# zamekKodowy_odbiornik.net
KiCad netlist of a schematic drawn in EAGLE
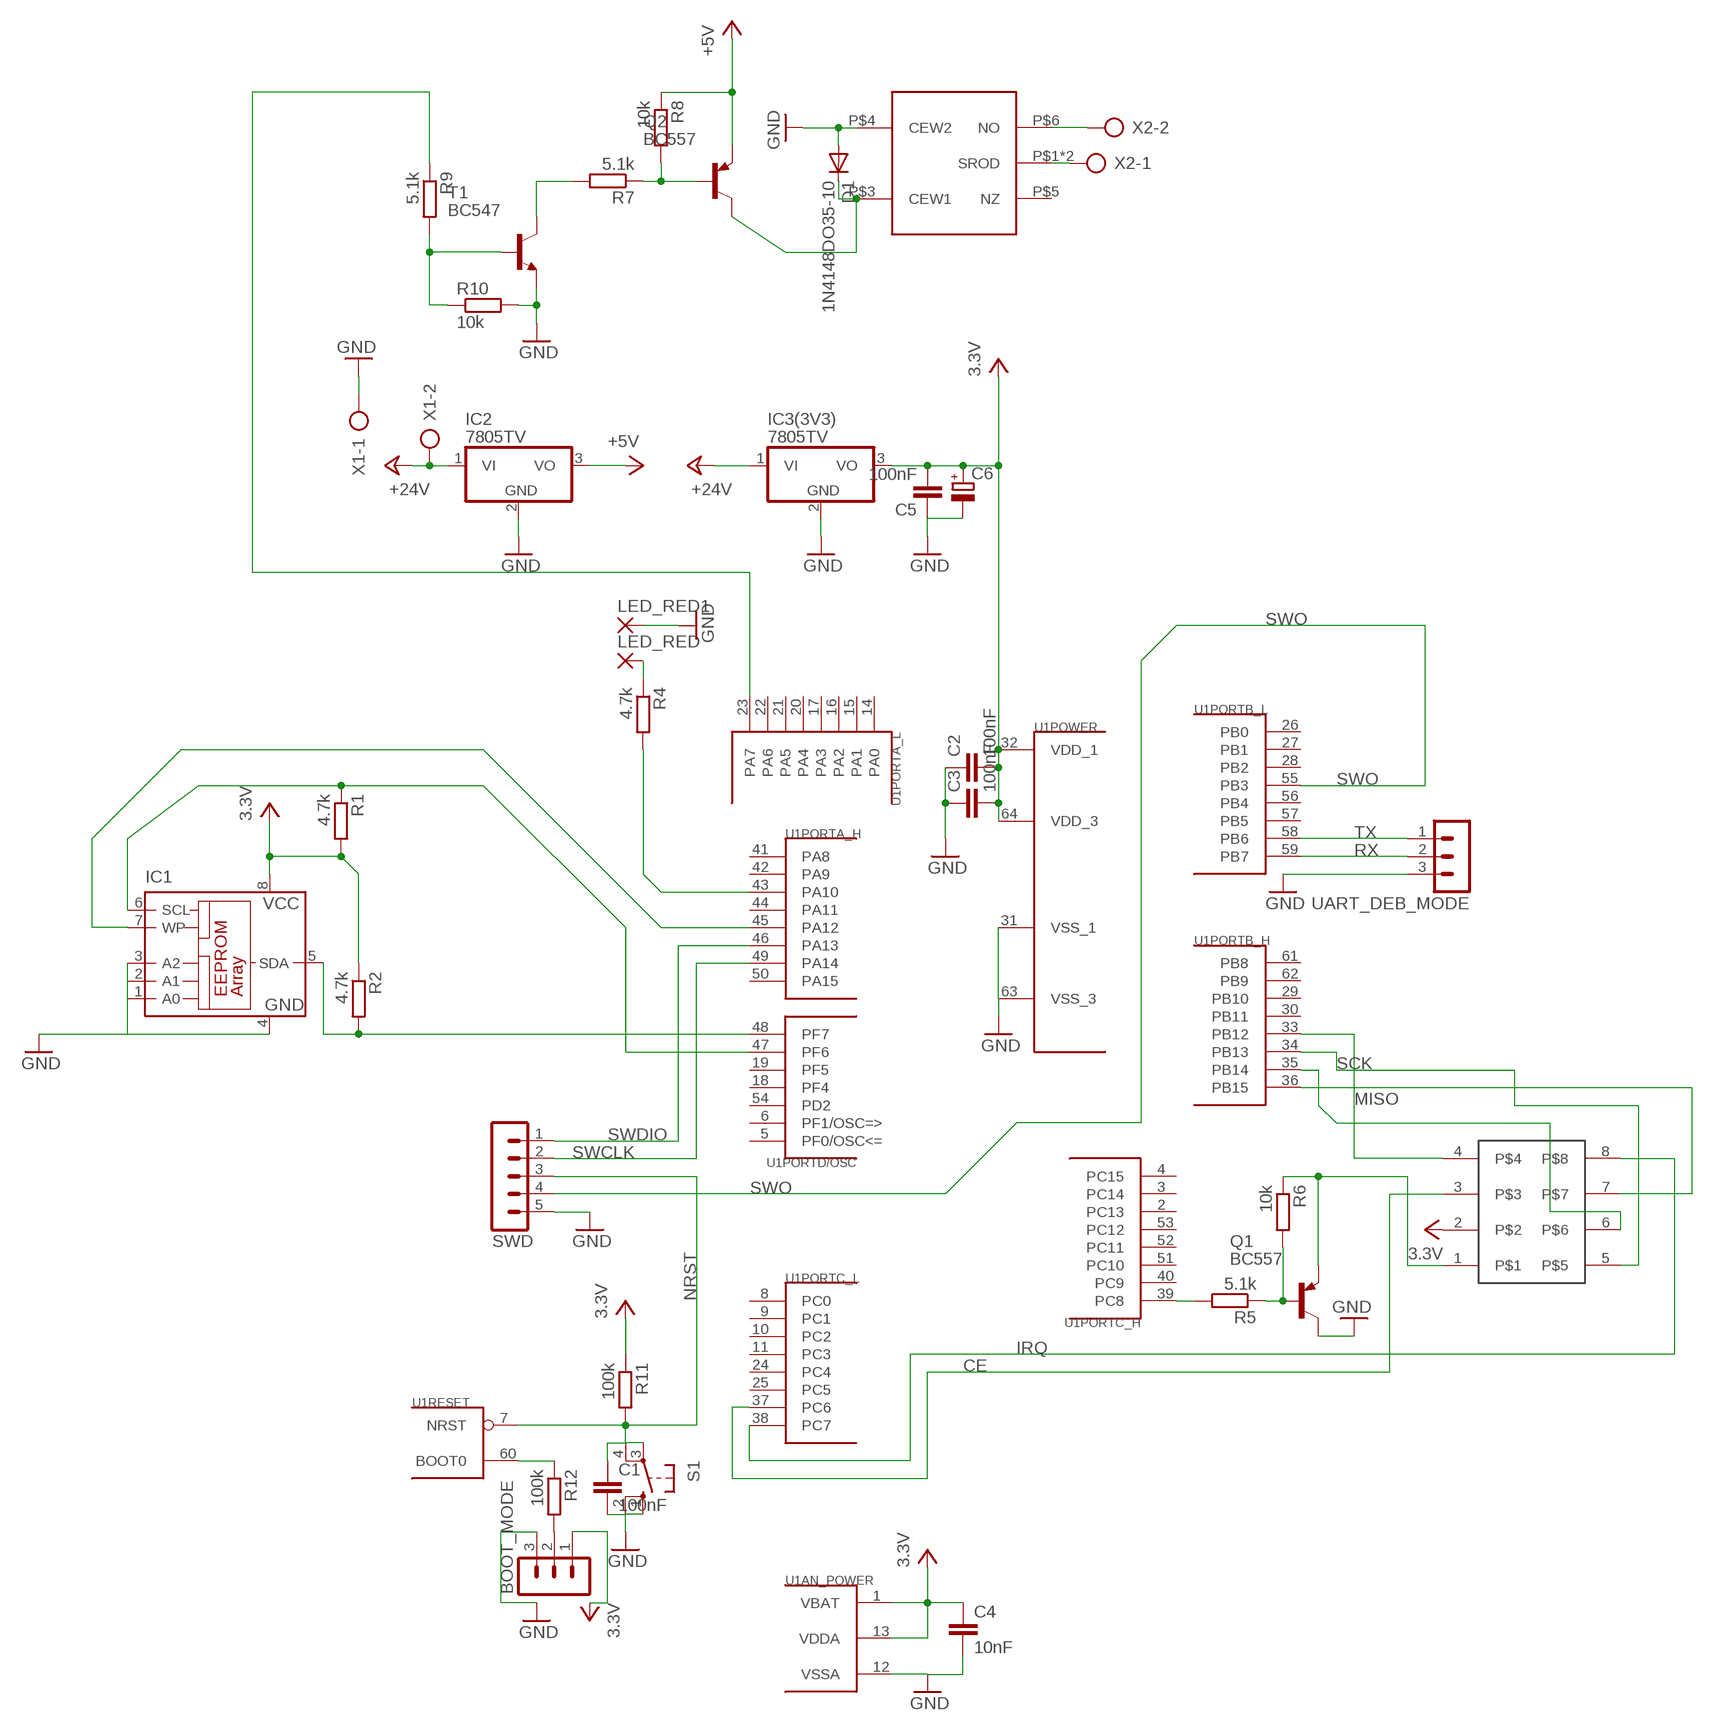
[diagram p0: schematic, sheet 1]

(export (version "E")
  (design (tool "Eeschema 10.0.6"))
  (components
    (comp (ref "BOOT_MODE")
      (value "MA03-1")
      (footprint "eagle-import:MA03-1")
      (fields (field (name "OC_FARNELL") "unknown") (field (name "OC_NEWARK") "unknown"))
      (libsource (lib "eagle-import") (part "MA03-1"))
    )
    (comp (ref "C1")
      (value "100nF")
      (footprint "eagle-import:C0603")
      (libsource (lib "eagle-import") (part "C-EUC0603"))
    )
    (comp (ref "C2")
      (value "100nF")
      (footprint "eagle-import:C0603")
      (libsource (lib "eagle-import") (part "C-EUC0603"))
    )
    (comp (ref "C3")
      (value "100nF")
      (footprint "eagle-import:C0603")
      (libsource (lib "eagle-import") (part "C-EUC0603"))
    )
    (comp (ref "C4")
      (value "10nF")
      (footprint "eagle-import:C0603")
      (libsource (lib "eagle-import") (part "C-EUC0603"))
    )
    (comp (ref "C5")
      (value "100nF")
      (footprint "eagle-import:C0603")
      (libsource (lib "eagle-import") (part "C-EUC0603"))
    )
    (comp (ref "C6")
      (value "CPOL-EUE2-5")
      (footprint "eagle-import:E2-5")
      (libsource (lib "eagle-import") (part "CPOL-EUE2-5"))
    )
    (comp (ref "CON1")
      (value "CON10")
      (footprint "eagle-import:CON10")
      (libsource (lib "eagle-import") (part "CON10"))
    )
    (comp (ref "D1")
      (value "1N4148DO35-10")
      (footprint "eagle-import:DO35-10")
      (libsource (lib "eagle-import") (part "1N4148DO35-10"))
    )
    (comp (ref "IC1")
      (value "24C16BSN")
      (footprint "eagle-import:SO-08")
      (fields (field (name "MPN") "AT24C16BN-SH-B"))
      (libsource (lib "eagle-import") (part "24SNC16B"))
    )
    (comp (ref "IC2")
      (value "7805TV")
      (footprint "eagle-import:TO220V")
      (libsource (lib "eagle-import") (part "78TV05"))
    )
    (comp (ref "IC3(3V3)")
      (value "7805TV")
      (footprint "eagle-import:TO220V")
      (libsource (lib "eagle-import") (part "78TV05"))
    )
    (comp (ref "LED_RED")
      (value "2,54/0,9")
      (footprint "eagle-import:2,54_0,9")
      (libsource (lib "eagle-import") (part "2,54/0,9"))
    )
    (comp (ref "LED_RED1")
      (value "2,54/0,9")
      (footprint "eagle-import:2,54_0,9")
      (libsource (lib "eagle-import") (part "2,54/0,9"))
    )
    (comp (ref "Q1")
      (value "BC557")
      (footprint "eagle-import:TO92")
      (libsource (lib "eagle-import") (part "BC557"))
    )
    (comp (ref "Q2")
      (value "BC557")
      (footprint "eagle-import:TO92")
      (libsource (lib "eagle-import") (part "BC557"))
    )
    (comp (ref "R1")
      (value "4.7k")
      (footprint "eagle-import:R0603")
      (libsource (lib "eagle-import") (part "R-EU_R0603"))
    )
    (comp (ref "R2")
      (value "4.7k")
      (footprint "eagle-import:R0603")
      (libsource (lib "eagle-import") (part "R-EU_R0603"))
    )
    (comp (ref "R4")
      (value "4.7k")
      (footprint "eagle-import:R0603")
      (libsource (lib "eagle-import") (part "R-EU_R0603"))
    )
    (comp (ref "R5")
      (value "5.1k")
      (footprint "eagle-import:R0603")
      (libsource (lib "eagle-import") (part "R-EU_R0603"))
    )
    (comp (ref "R6")
      (value "10k")
      (footprint "eagle-import:R0603")
      (libsource (lib "eagle-import") (part "R-EU_R0603"))
    )
    (comp (ref "R7")
      (value "5.1k")
      (footprint "eagle-import:R0603")
      (libsource (lib "eagle-import") (part "R-EU_R0603"))
    )
    (comp (ref "R8")
      (value "10k")
      (footprint "eagle-import:R0603")
      (libsource (lib "eagle-import") (part "R-EU_R0603"))
    )
    (comp (ref "R9")
      (value "5.1k")
      (footprint "eagle-import:R0603")
      (libsource (lib "eagle-import") (part "R-EU_R0603"))
    )
    (comp (ref "R10")
      (value "10k")
      (footprint "eagle-import:R0603")
      (libsource (lib "eagle-import") (part "R-EU_R0603"))
    )
    (comp (ref "R11")
      (value "100k")
      (footprint "eagle-import:R0603")
      (libsource (lib "eagle-import") (part "R-EU_R0603"))
    )
    (comp (ref "R12")
      (value "100k")
      (footprint "eagle-import:R0603")
      (libsource (lib "eagle-import") (part "R-EU_R0603"))
    )
    (comp (ref "S1")
      (value "10-XX")
      (footprint "eagle-import:B3F-10XX")
      (fields (field (name "MPN") "B3F-1000"))
      (libsource (lib "eagle-import") (part "10-XX"))
    )
    (comp (ref "SWD")
      (value "MA05-1")
      (footprint "eagle-import:MA05-1")
      (libsource (lib "eagle-import") (part "MA05-1"))
    )
    (comp (ref "T1")
      (value "BC547")
      (footprint "eagle-import:TO92")
      (libsource (lib "eagle-import") (part "BC547"))
    )
    (comp (ref "U$1")
      (value "PRZEKAZ")
      (footprint "eagle-import:FPR")
      (libsource (lib "eagle-import") (part "PRZEKAZ"))
    )
    (comp (ref "U1")
      (value "STM32F10XRXT6")
      (footprint "eagle-import:TQFP64")
      (libsource (lib "eagle-import") (part "STM32F10XRXT6"))
    )
    (comp (ref "UART_DEB_MODE")
      (value "MA03-1")
      (footprint "eagle-import:MA03-1")
      (libsource (lib "eagle-import") (part "MA03-1"))
    )
    (comp (ref "X1")
      (value "AK300/2")
      (footprint "eagle-import:AK300_2")
      (libsource (lib "eagle-import") (part "AK300/2"))
    )
    (comp (ref "X2")
      (value "AK300/2")
      (footprint "eagle-import:AK300_2")
      (libsource (lib "eagle-import") (part "AK300/2"))
    )
  )
  (nets
    (net (code "1") (name "+5V") (class "Default")
      (node (ref "IC2") (pin "3") (pinfunction "VO_3") (pintype "passive"))
      (node (ref "Q2") (pin "1") (pinfunction "E_1") (pintype "passive"))
      (node (ref "R8") (pin "1") (pinfunction "1_1") (pintype "passive"))
    )
    (net (code "2") (name "+24V") (class "Default")
      (node (ref "IC2") (pin "1") (pinfunction "VI_1") (pintype "input"))
      (node (ref "IC3(3V3)") (pin "1") (pinfunction "VI_1") (pintype "input"))
      (node (ref "X1") (pin "2") (pinfunction "KL_2") (pintype "passive"))
    )
    (net (code "3") (name "/CE") (class "Default")
      (node (ref "CON1") (pin "3") (pinfunction "P$3_3") (pintype "bidirectional"))
      (node (ref "U1") (pin "37") (pinfunction "PC6_37") (pintype "bidirectional"))
    )
    (net (code "4") (name "/IRQ") (class "Default")
      (node (ref "CON1") (pin "8") (pinfunction "P$8_8") (pintype "bidirectional"))
      (node (ref "U1") (pin "38") (pinfunction "PC7_38") (pintype "bidirectional"))
    )
    (net (code "5") (name "/MISO") (class "Default")
      (node (ref "CON1") (pin "7") (pinfunction "P$7_7") (pintype "bidirectional"))
      (node (ref "U1") (pin "36") (pinfunction "PB15_36") (pintype "bidirectional"))
    )
    (net (code "6") (name "/NRST") (class "Default")
      (node (ref "C1") (pin "1") (pinfunction "1_1") (pintype "passive"))
      (node (ref "R11") (pin "2") (pinfunction "2_2") (pintype "passive"))
      (node (ref "S1") (pin "3") (pinfunction "P_3") (pintype "passive"))
      (node (ref "S1") (pin "4") (pinfunction "P1_4") (pintype "passive"))
      (node (ref "SWD") (pin "3") (pinfunction "3_3") (pintype "passive"))
      (node (ref "U1") (pin "7") (pinfunction "NRST_7") (pintype "input"))
    )
    (net (code "7") (name "/RX") (class "Default")
      (node (ref "U1") (pin "59") (pinfunction "PB7_59") (pintype "bidirectional"))
      (node (ref "UART_DEB_MODE") (pin "2") (pinfunction "2_2") (pintype "passive"))
    )
    (net (code "8") (name "/SCK") (class "Default")
      (node (ref "CON1") (pin "5") (pinfunction "P$5_5") (pintype "bidirectional"))
      (node (ref "U1") (pin "34") (pinfunction "PB13_34") (pintype "bidirectional"))
    )
    (net (code "9") (name "/SWCLK") (class "Default")
      (node (ref "SWD") (pin "2") (pinfunction "2_2") (pintype "passive"))
      (node (ref "U1") (pin "49") (pinfunction "PA14_49") (pintype "bidirectional"))
    )
    (net (code "10") (name "/SWDIO") (class "Default")
      (node (ref "SWD") (pin "1") (pinfunction "1_1") (pintype "passive"))
      (node (ref "U1") (pin "46") (pinfunction "PA13_46") (pintype "bidirectional"))
    )
    (net (code "11") (name "/SWO") (class "Default")
      (node (ref "SWD") (pin "4") (pinfunction "4_4") (pintype "passive"))
      (node (ref "U1") (pin "55") (pinfunction "PB3_55") (pintype "bidirectional"))
    )
    (net (code "12") (name "/TX") (class "Default")
      (node (ref "U1") (pin "58") (pinfunction "PB6_58") (pintype "bidirectional"))
      (node (ref "UART_DEB_MODE") (pin "1") (pinfunction "1_1") (pintype "passive"))
    )
    (net (code "13") (name "3.3V") (class "Default")
      (node (ref "BOOT_MODE") (pin "1") (pinfunction "1_1") (pintype "passive"))
      (node (ref "C2") (pin "2") (pinfunction "2_2") (pintype "passive"))
      (node (ref "C3") (pin "2") (pinfunction "2_2") (pintype "passive"))
      (node (ref "C4") (pin "1") (pinfunction "1_1") (pintype "passive"))
      (node (ref "C5") (pin "2") (pinfunction "2_2") (pintype "passive"))
      (node (ref "C6") (pin "+") (pinfunction "+_+") (pintype "passive"))
      (node (ref "CON1") (pin "2") (pinfunction "P$2_2") (pintype "bidirectional"))
      (node (ref "IC1") (pin "8") (pinfunction "VCC_8") (pintype "power_in"))
      (node (ref "IC3(3V3)") (pin "3") (pinfunction "VO_3") (pintype "passive"))
      (node (ref "R1") (pin "2") (pinfunction "2_2") (pintype "passive"))
      (node (ref "R11") (pin "1") (pinfunction "1_1") (pintype "passive"))
      (node (ref "R2") (pin "1") (pinfunction "1_1") (pintype "passive"))
      (node (ref "U1") (pin "1") (pinfunction "VBAT_1") (pintype "power_in"))
      (node (ref "U1") (pin "13") (pinfunction "VDDA_13") (pintype "power_in"))
      (node (ref "U1") (pin "32") (pinfunction "VDD_1_32") (pintype "power_in"))
      (node (ref "U1") (pin "64") (pinfunction "VDD_3_64") (pintype "power_in"))
    )
    (net (code "14") (name "GND") (class "Default")
      (node (ref "BOOT_MODE") (pin "3") (pinfunction "3_3") (pintype "passive"))
      (node (ref "C1") (pin "2") (pinfunction "2_2") (pintype "passive"))
      (node (ref "C2") (pin "1") (pinfunction "1_1") (pintype "passive"))
      (node (ref "C3") (pin "1") (pinfunction "1_1") (pintype "passive"))
      (node (ref "C4") (pin "2") (pinfunction "2_2") (pintype "passive"))
      (node (ref "C5") (pin "1") (pinfunction "1_1") (pintype "passive"))
      (node (ref "C6") (pin "-") (pinfunction "-_-") (pintype "passive"))
      (node (ref "D1") (pin "A") (pinfunction "A_A") (pintype "passive"))
      (node (ref "IC1") (pin "1") (pinfunction "A0_1") (pintype "input"))
      (node (ref "IC1") (pin "2") (pinfunction "A1_2") (pintype "input"))
      (node (ref "IC1") (pin "3") (pinfunction "A2_3") (pintype "input"))
      (node (ref "IC1") (pin "4") (pinfunction "GND_4") (pintype "power_in"))
      (node (ref "IC2") (pin "2") (pinfunction "GND_2") (pintype "passive"))
      (node (ref "IC3(3V3)") (pin "2") (pinfunction "GND_2") (pintype "passive"))
      (node (ref "LED_RED1") (pin "1") (pinfunction "P_1") (pintype "passive"))
      (node (ref "Q1") (pin "3") (pinfunction "C_3") (pintype "passive"))
      (node (ref "R10") (pin "2") (pinfunction "2_2") (pintype "passive"))
      (node (ref "S1") (pin "1") (pinfunction "S_1") (pintype "passive"))
      (node (ref "S1") (pin "2") (pinfunction "S1_2") (pintype "passive"))
      (node (ref "SWD") (pin "5") (pinfunction "5_5") (pintype "passive"))
      (node (ref "T1") (pin "1") (pinfunction "E_1") (pintype "passive"))
      (node (ref "U$1") (pin "P$4") (pinfunction "CEW2_P$4") (pintype "bidirectional"))
      (node (ref "U1") (pin "12") (pinfunction "VSSA_12") (pintype "power_in"))
      (node (ref "U1") (pin "31") (pinfunction "VSS_1_31") (pintype "power_in"))
      (node (ref "U1") (pin "63") (pinfunction "VSS_3_63") (pintype "power_in"))
      (node (ref "UART_DEB_MODE") (pin "3") (pinfunction "3_3") (pintype "passive"))
      (node (ref "X1") (pin "1") (pinfunction "KL_1") (pintype "passive"))
    )
    (net (code "15") (name "Net-(BOOT_MODE-Pad2)") (class "Default")
      (node (ref "BOOT_MODE") (pin "2") (pinfunction "2_2") (pintype "passive"))
      (node (ref "R12") (pin "2") (pinfunction "2_2") (pintype "passive"))
    )
    (net (code "16") (name "Net-(CON1-P$1)") (class "Default")
      (node (ref "CON1") (pin "1") (pinfunction "P$1_1") (pintype "bidirectional"))
      (node (ref "Q1") (pin "1") (pinfunction "E_1") (pintype "passive"))
      (node (ref "R6") (pin "1") (pinfunction "1_1") (pintype "passive"))
    )
    (net (code "17") (name "Net-(CON1-P$4)") (class "Default")
      (node (ref "CON1") (pin "4") (pinfunction "P$4_4") (pintype "bidirectional"))
      (node (ref "U1") (pin "33") (pinfunction "PB12_33") (pintype "bidirectional"))
    )
    (net (code "18") (name "Net-(CON1-P$6)") (class "Default")
      (node (ref "CON1") (pin "6") (pinfunction "P$6_6") (pintype "bidirectional"))
      (node (ref "U1") (pin "35") (pinfunction "PB14_35") (pintype "bidirectional"))
    )
    (net (code "19") (name "Net-(IC1-SCL)") (class "Default")
      (node (ref "IC1") (pin "6") (pinfunction "SCL_6") (pintype "input"))
      (node (ref "R1") (pin "1") (pinfunction "1_1") (pintype "passive"))
      (node (ref "U1") (pin "47") (pinfunction "PF6_47") (pintype "bidirectional"))
    )
    (net (code "20") (name "Net-(IC1-SDA)") (class "Default")
      (node (ref "IC1") (pin "5") (pinfunction "SDA_5") (pintype "bidirectional"))
      (node (ref "R2") (pin "2") (pinfunction "2_2") (pintype "passive"))
      (node (ref "U1") (pin "48") (pinfunction "PF7_48") (pintype "bidirectional"))
    )
    (net (code "21") (name "Net-(IC1-WP)") (class "Default")
      (node (ref "IC1") (pin "7") (pinfunction "WP_7") (pintype "input"))
      (node (ref "U1") (pin "45") (pinfunction "PA12_45") (pintype "bidirectional"))
    )
    (net (code "22") (name "Net-(LED_RED-P)") (class "Default")
      (node (ref "LED_RED") (pin "1") (pinfunction "P_1") (pintype "passive"))
      (node (ref "R4") (pin "1") (pinfunction "1_1") (pintype "passive"))
    )
    (net (code "23") (name "Net-(Q1-B)") (class "Default")
      (node (ref "Q1") (pin "2") (pinfunction "B_2") (pintype "passive"))
      (node (ref "R5") (pin "1") (pinfunction "1_1") (pintype "passive"))
      (node (ref "R6") (pin "2") (pinfunction "2_2") (pintype "passive"))
    )
    (net (code "24") (name "Net-(Q2-B)") (class "Default")
      (node (ref "Q2") (pin "2") (pinfunction "B_2") (pintype "passive"))
      (node (ref "R7") (pin "1") (pinfunction "1_1") (pintype "passive"))
      (node (ref "R8") (pin "2") (pinfunction "2_2") (pintype "passive"))
    )
    (net (code "25") (name "Net-(Q2-C)") (class "Default")
      (node (ref "D1") (pin "C") (pinfunction "C_C") (pintype "passive"))
      (node (ref "Q2") (pin "3") (pinfunction "C_3") (pintype "passive"))
      (node (ref "U$1") (pin "P$3") (pinfunction "CEW1_P$3") (pintype "bidirectional"))
    )
    (net (code "26") (name "Net-(T1-B)") (class "Default")
      (node (ref "R10") (pin "1") (pinfunction "1_1") (pintype "passive"))
      (node (ref "R9") (pin "2") (pinfunction "2_2") (pintype "passive"))
      (node (ref "T1") (pin "2") (pinfunction "B_2") (pintype "passive"))
    )
    (net (code "27") (name "Net-(T1-C)") (class "Default")
      (node (ref "R7") (pin "2") (pinfunction "2_2") (pintype "passive"))
      (node (ref "T1") (pin "3") (pinfunction "C_3") (pintype "passive"))
    )
    (net (code "28") (name "Net-(U$1-NO)") (class "Default")
      (node (ref "U$1") (pin "P$6") (pinfunction "NO_P$6") (pintype "bidirectional"))
      (node (ref "X2") (pin "2") (pinfunction "KL_2") (pintype "passive"))
    )
    (net (code "29") (name "Net-(U1B-PA10)") (class "Default")
      (node (ref "R4") (pin "2") (pinfunction "2_2") (pintype "passive"))
      (node (ref "U1") (pin "43") (pinfunction "PA10_43") (pintype "bidirectional"))
    )
    (net (code "30") (name "Net-(U1C-PA7)") (class "Default")
      (node (ref "R9") (pin "1") (pinfunction "1_1") (pintype "passive"))
      (node (ref "U1") (pin "23") (pinfunction "PA7_23") (pintype "bidirectional"))
    )
    (net (code "31") (name "Net-(U1F-PC8)") (class "Default")
      (node (ref "R5") (pin "2") (pinfunction "2_2") (pintype "passive"))
      (node (ref "U1") (pin "39") (pinfunction "PC8_39") (pintype "bidirectional"))
    )
    (net (code "32") (name "Net-(U1J-BOOT0)") (class "Default")
      (node (ref "R12") (pin "1") (pinfunction "1_1") (pintype "passive"))
      (node (ref "U1") (pin "60") (pinfunction "BOOT0_60") (pintype "input"))
    )
    (net (code "33") (name "Net-(X2A-KL)") (class "Default")
      (node (ref "U$1") (pin "P$1") (pinfunction "SROD_P$1") (pintype "bidirectional"))
      (node (ref "U$1") (pin "P$2") (pinfunction "SROD_P$2") (pintype "bidirectional"))
      (node (ref "X2") (pin "1") (pinfunction "KL_1") (pintype "passive"))
    )
    (net (code "34") (name "unconnected-(U$1-NZ-PadP$5)") (class "Default")
      (node (ref "U$1") (pin "P$5") (pinfunction "NZ_P$5") (pintype "bidirectional"))
    )
    (net (code "35") (name "unconnected-(U1B-PA8-Pad41)") (class "Default")
      (node (ref "U1") (pin "41") (pinfunction "PA8_41") (pintype "bidirectional"))
    )
    (net (code "36") (name "unconnected-(U1B-PA9-Pad42)") (class "Default")
      (node (ref "U1") (pin "42") (pinfunction "PA9_42") (pintype "bidirectional"))
    )
    (net (code "37") (name "unconnected-(U1B-PA11-Pad44)") (class "Default")
      (node (ref "U1") (pin "44") (pinfunction "PA11_44") (pintype "bidirectional"))
    )
    (net (code "38") (name "unconnected-(U1B-PA15-Pad50)") (class "Default")
      (node (ref "U1") (pin "50") (pinfunction "PA15_50") (pintype "bidirectional"))
    )
    (net (code "39") (name "unconnected-(U1C-PA0-Pad14)") (class "Default")
      (node (ref "U1") (pin "14") (pinfunction "PA0_14") (pintype "bidirectional"))
    )
    (net (code "40") (name "unconnected-(U1C-PA1-Pad15)") (class "Default")
      (node (ref "U1") (pin "15") (pinfunction "PA1_15") (pintype "bidirectional"))
    )
    (net (code "41") (name "unconnected-(U1C-PA2-Pad16)") (class "Default")
      (node (ref "U1") (pin "16") (pinfunction "PA2_16") (pintype "bidirectional"))
    )
    (net (code "42") (name "unconnected-(U1C-PA3-Pad17)") (class "Default")
      (node (ref "U1") (pin "17") (pinfunction "PA3_17") (pintype "bidirectional"))
    )
    (net (code "43") (name "unconnected-(U1C-PA4-Pad20)") (class "Default")
      (node (ref "U1") (pin "20") (pinfunction "PA4_20") (pintype "bidirectional"))
    )
    (net (code "44") (name "unconnected-(U1C-PA5-Pad21)") (class "Default")
      (node (ref "U1") (pin "21") (pinfunction "PA5_21") (pintype "bidirectional"))
    )
    (net (code "45") (name "unconnected-(U1C-PA6-Pad22)") (class "Default")
      (node (ref "U1") (pin "22") (pinfunction "PA6_22") (pintype "bidirectional"))
    )
    (net (code "46") (name "unconnected-(U1D-PB8-Pad61)") (class "Default")
      (node (ref "U1") (pin "61") (pinfunction "PB8_61") (pintype "bidirectional"))
    )
    (net (code "47") (name "unconnected-(U1D-PB9-Pad62)") (class "Default")
      (node (ref "U1") (pin "62") (pinfunction "PB9_62") (pintype "bidirectional"))
    )
    (net (code "48") (name "unconnected-(U1D-PB10-Pad29)") (class "Default")
      (node (ref "U1") (pin "29") (pinfunction "PB10_29") (pintype "bidirectional"))
    )
    (net (code "49") (name "unconnected-(U1D-PB11-Pad30)") (class "Default")
      (node (ref "U1") (pin "30") (pinfunction "PB11_30") (pintype "bidirectional"))
    )
    (net (code "50") (name "unconnected-(U1E-PB0-Pad26)") (class "Default")
      (node (ref "U1") (pin "26") (pinfunction "PB0_26") (pintype "bidirectional"))
    )
    (net (code "51") (name "unconnected-(U1E-PB1-Pad27)") (class "Default")
      (node (ref "U1") (pin "27") (pinfunction "PB1_27") (pintype "bidirectional"))
    )
    (net (code "52") (name "unconnected-(U1E-PB2-Pad28)") (class "Default")
      (node (ref "U1") (pin "28") (pinfunction "PB2_28") (pintype "bidirectional"))
    )
    (net (code "53") (name "unconnected-(U1E-PB4-Pad56)") (class "Default")
      (node (ref "U1") (pin "56") (pinfunction "PB4_56") (pintype "bidirectional"))
    )
    (net (code "54") (name "unconnected-(U1E-PB5-Pad57)") (class "Default")
      (node (ref "U1") (pin "57") (pinfunction "PB5_57") (pintype "bidirectional"))
    )
    (net (code "55") (name "unconnected-(U1F-PC9-Pad40)") (class "Default")
      (node (ref "U1") (pin "40") (pinfunction "PC9_40") (pintype "bidirectional"))
    )
    (net (code "56") (name "unconnected-(U1F-PC10-Pad51)") (class "Default")
      (node (ref "U1") (pin "51") (pinfunction "PC10_51") (pintype "bidirectional"))
    )
    (net (code "57") (name "unconnected-(U1F-PC11-Pad52)") (class "Default")
      (node (ref "U1") (pin "52") (pinfunction "PC11_52") (pintype "bidirectional"))
    )
    (net (code "58") (name "unconnected-(U1F-PC12-Pad53)") (class "Default")
      (node (ref "U1") (pin "53") (pinfunction "PC12_53") (pintype "bidirectional"))
    )
    (net (code "59") (name "unconnected-(U1F-PC13-Pad2)") (class "Default")
      (node (ref "U1") (pin "2") (pinfunction "PC13_2") (pintype "bidirectional"))
    )
    (net (code "60") (name "unconnected-(U1F-PC14-Pad3)") (class "Default")
      (node (ref "U1") (pin "3") (pinfunction "PC14_3") (pintype "bidirectional"))
    )
    (net (code "61") (name "unconnected-(U1F-PC15-Pad4)") (class "Default")
      (node (ref "U1") (pin "4") (pinfunction "PC15_4") (pintype "bidirectional"))
    )
    (net (code "62") (name "unconnected-(U1G-PC0-Pad8)") (class "Default")
      (node (ref "U1") (pin "8") (pinfunction "PC0_8") (pintype "bidirectional"))
    )
    (net (code "63") (name "unconnected-(U1G-PC1-Pad9)") (class "Default")
      (node (ref "U1") (pin "9") (pinfunction "PC1_9") (pintype "bidirectional"))
    )
    (net (code "64") (name "unconnected-(U1G-PC2-Pad10)") (class "Default")
      (node (ref "U1") (pin "10") (pinfunction "PC2_10") (pintype "bidirectional"))
    )
    (net (code "65") (name "unconnected-(U1G-PC3-Pad11)") (class "Default")
      (node (ref "U1") (pin "11") (pinfunction "PC3_11") (pintype "bidirectional"))
    )
    (net (code "66") (name "unconnected-(U1G-PC4-Pad24)") (class "Default")
      (node (ref "U1") (pin "24") (pinfunction "PC4_24") (pintype "bidirectional"))
    )
    (net (code "67") (name "unconnected-(U1G-PC5-Pad25)") (class "Default")
      (node (ref "U1") (pin "25") (pinfunction "PC5_25") (pintype "bidirectional"))
    )
    (net (code "68") (name "unconnected-(U1H-PD2-Pad54)") (class "Default")
      (node (ref "U1") (pin "54") (pinfunction "PD2_54") (pintype "bidirectional"))
    )
    (net (code "69") (name "unconnected-(U1H-PF0{slash}OSC<=-Pad5)") (class "Default")
      (node (ref "U1") (pin "5") (pinfunction "PF0/OSC<=_5") (pintype "bidirectional"))
    )
    (net (code "70") (name "unconnected-(U1H-PF1{slash}OSC=>-Pad6)") (class "Default")
      (node (ref "U1") (pin "6") (pinfunction "PF1/OSC=>_6") (pintype "bidirectional"))
    )
    (net (code "71") (name "unconnected-(U1H-PF4-Pad18)") (class "Default")
      (node (ref "U1") (pin "18") (pinfunction "PF4_18") (pintype "bidirectional"))
    )
    (net (code "72") (name "unconnected-(U1H-PF5-Pad19)") (class "Default")
      (node (ref "U1") (pin "19") (pinfunction "PF5_19") (pintype "bidirectional"))
    )
  )
)
